# PWM.net
KiCad netlist of a schematic drawn in Altium Designer
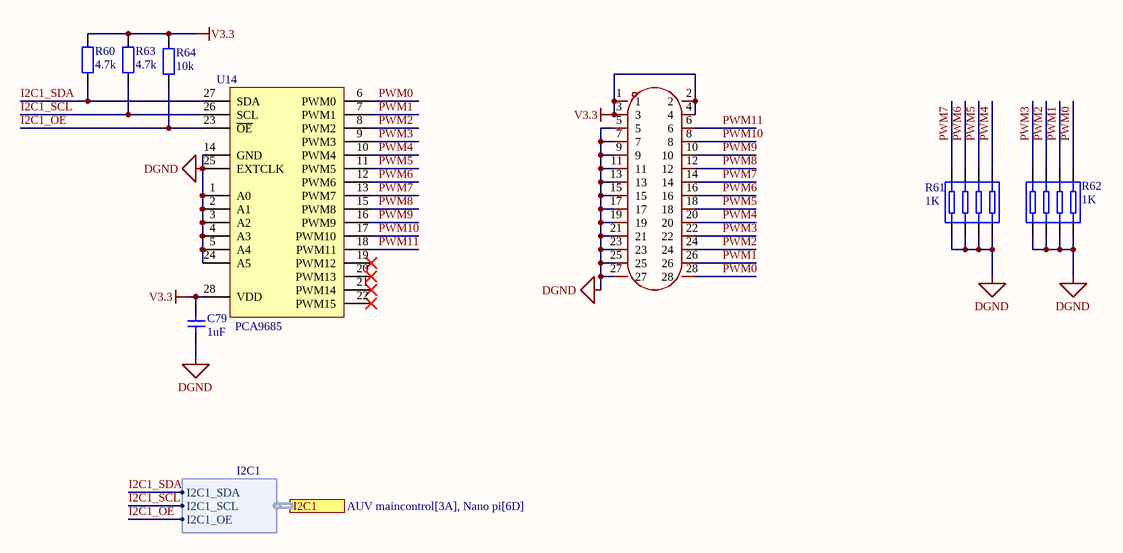
[diagram p0: PWM.SchDoc]

(export (version "E")
  (design (tool "Eeschema 10.0.6"))
  (components
    (comp (ref "C79")
      (value "1uF")
      (footprint "0603_C")
      (description "无极贴片电容")
      (libsource (lib "集大电协1.5") (part "Cap1"))
    )
    (comp (ref "R60")
      (value "4.7k")
      (footprint "0603R")
      (description "电阻")
      (libsource (lib "PBK11") (part "Res"))
    )
    (comp (ref "R61")
      (value "1K")
      (footprint "res-4")
      (description "排阻")
      (libsource (lib "集大电协1.5") (part "Res-4"))
    )
    (comp (ref "R62")
      (value "1K")
      (footprint "res-4")
      (description "排阻")
      (libsource (lib "集大电协1.5") (part "Res-4"))
    )
    (comp (ref "R63")
      (value "4.7k")
      (footprint "0603R")
      (description "电阻")
      (libsource (lib "PBK11") (part "Res"))
    )
    (comp (ref "R64")
      (value "10k")
      (footprint "0603R")
      (description "电阻")
      (libsource (lib "PBK11") (part "Res"))
    )
    (comp (ref "U14") (value "PCA9685") (footprint "TSSOP-28") (libsource (lib "集大电协1.5") (part "PCA9685")))
    (comp (ref "U15")
      (value "XDFH-0254-2*14P")
      (footprint "CONN-TH_28P-P2.54_LX_XDFH-0254-2X14P")
      (fields (field (name "MANUFACTURER") "LX(连欣科技)"))
      (libsource (lib "PBK11") (part "XDFH-0254-2*14P"))
    )
  )
  (nets
    (net (code "2") (name "/I2C1_OE") (class "Default")
      (node (ref "R64") (pin "1") (pinfunction "1_1") (pintype "passive"))
      (node (ref "U14") (pin "23") (pinfunction "~{OE}_23") (pintype "passive"))
    )
    (net (code "3") (name "/I2C1_SCL") (class "Default")
      (node (ref "R63") (pin "1") (pinfunction "1_1") (pintype "passive"))
      (node (ref "U14") (pin "26") (pinfunction "SCL_26") (pintype "passive"))
    )
    (net (code "4") (name "/I2C1_SDA") (class "Default")
      (node (ref "R60") (pin "1") (pinfunction "1_1") (pintype "passive"))
      (node (ref "U14") (pin "27") (pinfunction "SDA_27") (pintype "passive"))
    )
    (net (code "5") (name "/PWM0") (class "Default")
      (node (ref "R62") (pin "5") (pinfunction "5_5") (pintype "passive"))
      (node (ref "U14") (pin "6") (pinfunction "PWM0_6") (pintype "passive"))
      (node (ref "U15") (pin "28") (pinfunction "28_28") (pintype "passive"))
    )
    (net (code "6") (name "/PWM1") (class "Default")
      (node (ref "R62") (pin "6") (pinfunction "6_6") (pintype "passive"))
      (node (ref "U14") (pin "7") (pinfunction "PWM1_7") (pintype "passive"))
      (node (ref "U15") (pin "26") (pinfunction "26_26") (pintype "passive"))
    )
    (net (code "7") (name "/PWM2") (class "Default")
      (node (ref "R62") (pin "7") (pinfunction "7_7") (pintype "passive"))
      (node (ref "U14") (pin "8") (pinfunction "PWM2_8") (pintype "passive"))
      (node (ref "U15") (pin "24") (pinfunction "24_24") (pintype "passive"))
    )
    (net (code "8") (name "/PWM3") (class "Default")
      (node (ref "R62") (pin "8") (pinfunction "8_8") (pintype "passive"))
      (node (ref "U14") (pin "9") (pinfunction "PWM3_9") (pintype "passive"))
      (node (ref "U15") (pin "22") (pinfunction "22_22") (pintype "passive"))
    )
    (net (code "9") (name "/PWM4") (class "Default")
      (node (ref "R61") (pin "5") (pinfunction "5_5") (pintype "passive"))
      (node (ref "U14") (pin "10") (pinfunction "PWM4_10") (pintype "passive"))
      (node (ref "U15") (pin "20") (pinfunction "20_20") (pintype "passive"))
    )
    (net (code "10") (name "/PWM5") (class "Default")
      (node (ref "R61") (pin "6") (pinfunction "6_6") (pintype "passive"))
      (node (ref "U14") (pin "11") (pinfunction "PWM5_11") (pintype "passive"))
      (node (ref "U15") (pin "18") (pinfunction "18_18") (pintype "passive"))
    )
    (net (code "11") (name "/PWM6") (class "Default")
      (node (ref "R61") (pin "7") (pinfunction "7_7") (pintype "passive"))
      (node (ref "U14") (pin "12") (pinfunction "PWM6_12") (pintype "passive"))
      (node (ref "U15") (pin "16") (pinfunction "16_16") (pintype "passive"))
    )
    (net (code "12") (name "/PWM7") (class "Default")
      (node (ref "R61") (pin "8") (pinfunction "8_8") (pintype "passive"))
      (node (ref "U14") (pin "13") (pinfunction "PWM7_13") (pintype "passive"))
      (node (ref "U15") (pin "14") (pinfunction "14_14") (pintype "passive"))
    )
    (net (code "13") (name "/PWM8") (class "Default")
      (node (ref "U14") (pin "15") (pinfunction "PWM8_15") (pintype "passive"))
      (node (ref "U15") (pin "12") (pinfunction "12_12") (pintype "passive"))
    )
    (net (code "14") (name "/PWM9") (class "Default")
      (node (ref "U14") (pin "16") (pinfunction "PWM9_16") (pintype "passive"))
      (node (ref "U15") (pin "10") (pinfunction "10_10") (pintype "passive"))
    )
    (net (code "15") (name "/PWM10") (class "Default")
      (node (ref "U14") (pin "17") (pinfunction "PWM10_17") (pintype "passive"))
      (node (ref "U15") (pin "8") (pinfunction "8_8") (pintype "passive"))
    )
    (net (code "16") (name "/PWM11") (class "Default")
      (node (ref "U14") (pin "18") (pinfunction "PWM11_18") (pintype "passive"))
      (node (ref "U15") (pin "6") (pinfunction "6_6") (pintype "passive"))
    )
    (net (code "18") (name "DGND") (class "Default")
      (node (ref "C79") (pin "1") (pinfunction "1_1") (pintype "passive"))
      (node (ref "R61") (pin "1") (pinfunction "1_1") (pintype "passive"))
      (node (ref "R61") (pin "2") (pinfunction "2_2") (pintype "passive"))
      (node (ref "R61") (pin "3") (pinfunction "3_3") (pintype "passive"))
      (node (ref "R61") (pin "4") (pinfunction "4_4") (pintype "passive"))
      (node (ref "R62") (pin "1") (pinfunction "1_1") (pintype "passive"))
      (node (ref "R62") (pin "2") (pinfunction "2_2") (pintype "passive"))
      (node (ref "R62") (pin "3") (pinfunction "3_3") (pintype "passive"))
      (node (ref "R62") (pin "4") (pinfunction "4_4") (pintype "passive"))
      (node (ref "U14") (pin "1") (pinfunction "A0_1") (pintype "passive"))
      (node (ref "U14") (pin "14") (pinfunction "GND_14") (pintype "passive"))
      (node (ref "U14") (pin "2") (pinfunction "A1_2") (pintype "passive"))
      (node (ref "U14") (pin "24") (pinfunction "A5_24") (pintype "passive"))
      (node (ref "U14") (pin "25") (pinfunction "EXTCLK_25") (pintype "passive"))
      (node (ref "U14") (pin "3") (pinfunction "A2_3") (pintype "passive"))
      (node (ref "U14") (pin "4") (pinfunction "A3_4") (pintype "passive"))
      (node (ref "U14") (pin "5") (pinfunction "A4_5") (pintype "passive"))
      (node (ref "U15") (pin "11") (pinfunction "11_11") (pintype "passive"))
      (node (ref "U15") (pin "13") (pinfunction "13_13") (pintype "passive"))
      (node (ref "U15") (pin "15") (pinfunction "15_15") (pintype "passive"))
      (node (ref "U15") (pin "17") (pinfunction "17_17") (pintype "passive"))
      (node (ref "U15") (pin "19") (pinfunction "19_19") (pintype "passive"))
      (node (ref "U15") (pin "21") (pinfunction "21_21") (pintype "passive"))
      (node (ref "U15") (pin "23") (pinfunction "23_23") (pintype "passive"))
      (node (ref "U15") (pin "25") (pinfunction "25_25") (pintype "passive"))
      (node (ref "U15") (pin "27") (pinfunction "27_27") (pintype "passive"))
      (node (ref "U15") (pin "5") (pinfunction "5_5") (pintype "passive"))
      (node (ref "U15") (pin "7") (pinfunction "7_7") (pintype "passive"))
      (node (ref "U15") (pin "9") (pinfunction "9_9") (pintype "passive"))
    )
    (net (code "19") (name "V3.3") (class "Default")
      (node (ref "C79") (pin "2") (pinfunction "2_2") (pintype "passive"))
      (node (ref "R60") (pin "2") (pinfunction "2_2") (pintype "passive"))
      (node (ref "R63") (pin "2") (pinfunction "2_2") (pintype "passive"))
      (node (ref "R64") (pin "2") (pinfunction "2_2") (pintype "passive"))
      (node (ref "U14") (pin "28") (pinfunction "VDD_28") (pintype "passive"))
      (node (ref "U15") (pin "1") (pinfunction "1_1") (pintype "passive"))
      (node (ref "U15") (pin "2") (pinfunction "2_2") (pintype "passive"))
      (node (ref "U15") (pin "3") (pinfunction "3_3") (pintype "passive"))
      (node (ref "U15") (pin "4") (pinfunction "4_4") (pintype "passive"))
    )
    (net (code "20") (name "unconnected-(U14-PWM12-Pad19)") (class "Default")
      (node (ref "U14") (pin "19") (pinfunction "PWM12_19") (pintype "passive+no_connect"))
    )
    (net (code "21") (name "unconnected-(U14-PWM13-Pad20)") (class "Default")
      (node (ref "U14") (pin "20") (pinfunction "PWM13_20") (pintype "passive+no_connect"))
    )
    (net (code "22") (name "unconnected-(U14-PWM14-Pad21)") (class "Default")
      (node (ref "U14") (pin "21") (pinfunction "PWM14_21") (pintype "passive+no_connect"))
    )
    (net (code "23") (name "unconnected-(U14-PWM15-Pad22)") (class "Default")
      (node (ref "U14") (pin "22") (pinfunction "PWM15_22") (pintype "passive+no_connect"))
    )
  )
)
